# Sheet.net
KiCad netlist of a schematic drawn in Altium Designer
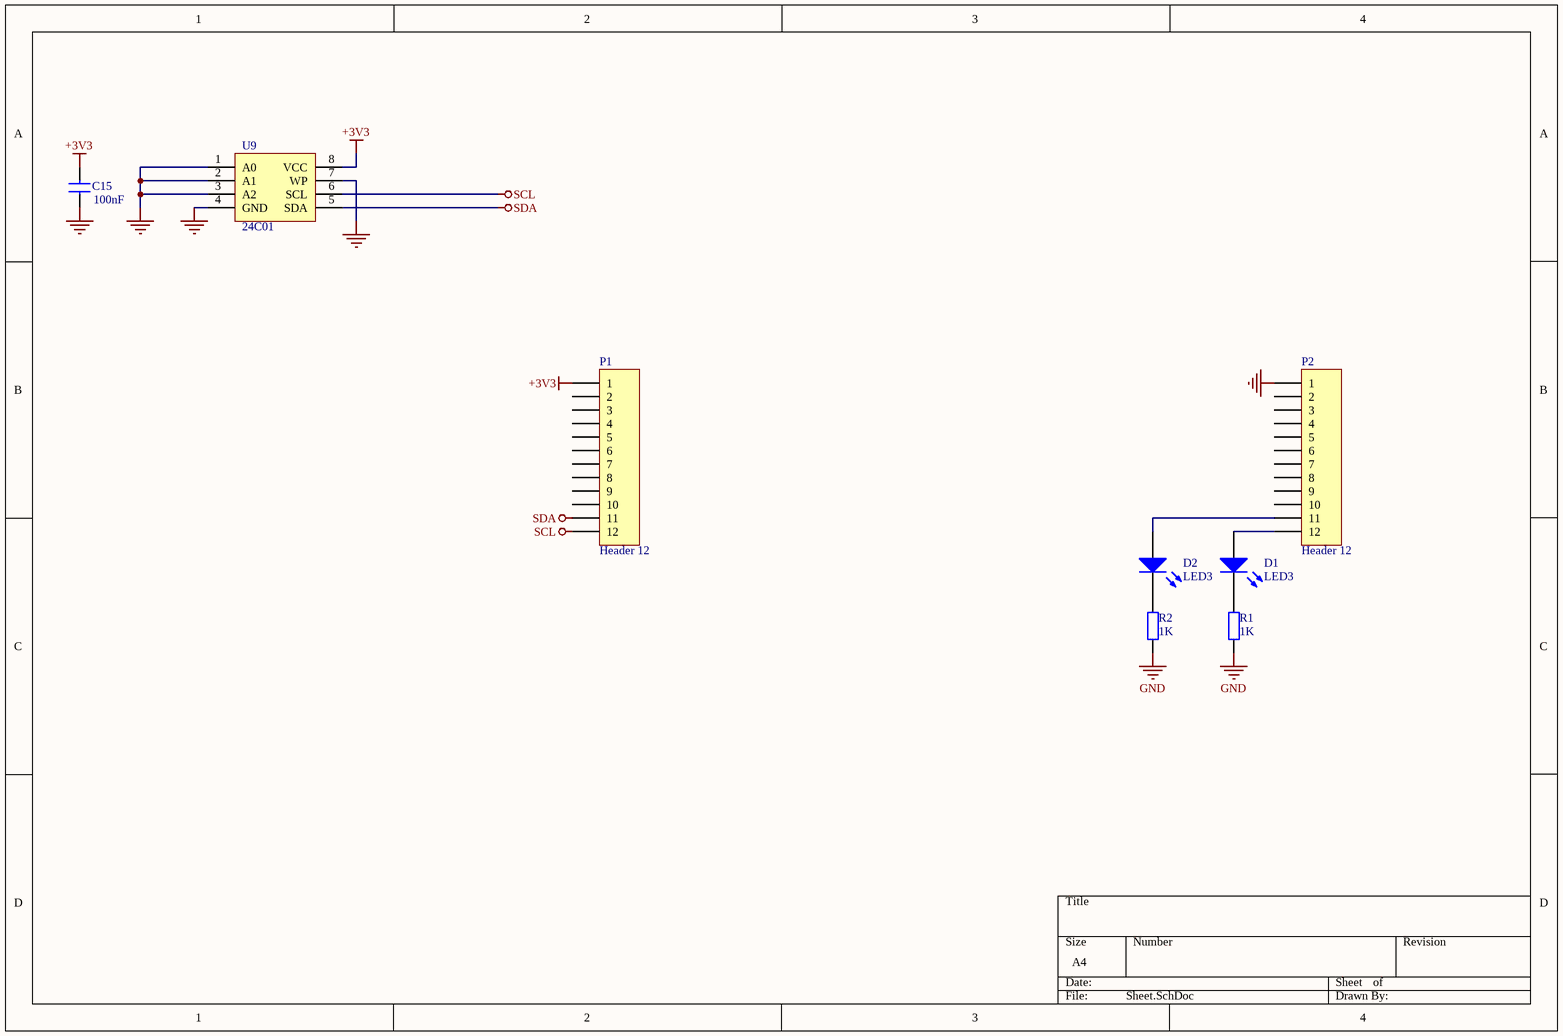
[diagram p0: Sheet.SchDoc]

(export (version "E")
  (design (tool "Eeschema 10.0.6"))
  (components
    (comp (ref "C15")
      (value "100nF")
      (footprint "RESC2012X65M")
      (description "Capacitor")
      (libsource (lib "*") (part "CAP"))
    )
    (comp (ref "D1")
      (value "LED3")
      (footprint "Led 0805")
      (description "Typical BLUE SiC LED")
      (fields (field (name "PUBLISHER") "Altium Limited"))
      (libsource (lib "Miscellaneous Devices") (part "LED3"))
    )
    (comp (ref "D2")
      (value "LED3")
      (footprint "Led 0805")
      (description "Typical BLUE SiC LED")
      (fields (field (name "PUBLISHER") "Altium Limited"))
      (libsource (lib "Miscellaneous Devices") (part "LED3"))
    )
    (comp (ref "P1")
      (value "Header 12")
      (footprint "HDR1X12")
      (description "Header, 12-Pin")
      (fields (field (name "PUBLISHER") "Altium Limited"))
      (libsource (lib "Miscellaneous Connectors") (part "Header 12"))
    )
    (comp (ref "P2")
      (value "Header 12")
      (footprint "HDR1X12")
      (description "Header, 12-Pin")
      (fields (field (name "PUBLISHER") "Altium Limited"))
      (libsource (lib "Miscellaneous Connectors") (part "Header 12"))
    )
    (comp (ref "R1")
      (value "1K")
      (footprint "0805")
      (description "Resistor")
      (fields (field (name "PUBLISHER") "Altium Limited"))
      (libsource (lib "Miscellaneous Devices") (part "Res2"))
    )
    (comp (ref "R2")
      (value "1K")
      (footprint "0805")
      (description "Resistor")
      (fields (field (name "PUBLISHER") "Altium Limited"))
      (libsource (lib "Miscellaneous Devices") (part "Res2"))
    )
    (comp (ref "U9") (value "24C01") (footprint "SO-8") (libsource (lib "Schlib1") (part "24C01")))
  )
  (nets
    (net (code "1") (name "+3V3") (class "Default")
      (node (ref "C15") (pin "1") (pinfunction "1_1") (pintype "passive"))
      (node (ref "P1") (pin "1") (pinfunction "1_1") (pintype "passive"))
      (node (ref "U9") (pin "8") (pinfunction "VCC_8") (pintype "power_in"))
    )
    (net (code "2") (name "GND") (class "Default")
      (node (ref "C15") (pin "2") (pinfunction "2_2") (pintype "passive"))
      (node (ref "P2") (pin "1") (pinfunction "1_1") (pintype "passive"))
      (node (ref "R1") (pin "1") (pinfunction "1_1") (pintype "passive"))
      (node (ref "R2") (pin "1") (pinfunction "1_1") (pintype "passive"))
      (node (ref "U9") (pin "1") (pinfunction "A0_1") (pintype "passive"))
      (node (ref "U9") (pin "2") (pinfunction "A1_2") (pintype "passive"))
      (node (ref "U9") (pin "3") (pinfunction "A2_3") (pintype "passive"))
      (node (ref "U9") (pin "4") (pinfunction "GND_4") (pintype "power_in"))
      (node (ref "U9") (pin "7") (pinfunction "WP_7") (pintype "passive"))
    )
    (net (code "3") (name "Net-(D1-A)") (class "Default")
      (node (ref "D1") (pin "1") (pinfunction "A_1") (pintype "passive"))
      (node (ref "P2") (pin "12") (pinfunction "12_12") (pintype "passive"))
    )
    (net (code "4") (name "Net-(D1-K)") (class "Default")
      (node (ref "D1") (pin "2") (pinfunction "K_2") (pintype "passive"))
      (node (ref "R1") (pin "2") (pinfunction "2_2") (pintype "passive"))
    )
    (net (code "5") (name "Net-(D2-A)") (class "Default")
      (node (ref "D2") (pin "1") (pinfunction "A_1") (pintype "passive"))
      (node (ref "P2") (pin "11") (pinfunction "11_11") (pintype "passive"))
    )
    (net (code "6") (name "Net-(D2-K)") (class "Default")
      (node (ref "D2") (pin "2") (pinfunction "K_2") (pintype "passive"))
      (node (ref "R2") (pin "2") (pinfunction "2_2") (pintype "passive"))
    )
    (net (code "7") (name "SCL") (class "Default")
      (node (ref "P1") (pin "12") (pinfunction "12_12") (pintype "passive"))
      (node (ref "U9") (pin "6") (pinfunction "SCL_6") (pintype "passive"))
    )
    (net (code "8") (name "SDA") (class "Default")
      (node (ref "P1") (pin "11") (pinfunction "11_11") (pintype "passive"))
      (node (ref "U9") (pin "5") (pinfunction "SDA_5") (pintype "passive"))
    )
    (net (code "9") (name "unconnected-(P1-Pad2)") (class "Default")
      (node (ref "P1") (pin "2") (pinfunction "2_2") (pintype "passive"))
    )
    (net (code "10") (name "unconnected-(P1-Pad3)") (class "Default")
      (node (ref "P1") (pin "3") (pinfunction "3_3") (pintype "passive"))
    )
    (net (code "11") (name "unconnected-(P1-Pad4)") (class "Default")
      (node (ref "P1") (pin "4") (pinfunction "4_4") (pintype "passive"))
    )
    (net (code "12") (name "unconnected-(P1-Pad5)") (class "Default")
      (node (ref "P1") (pin "5") (pinfunction "5_5") (pintype "passive"))
    )
    (net (code "13") (name "unconnected-(P1-Pad6)") (class "Default")
      (node (ref "P1") (pin "6") (pinfunction "6_6") (pintype "passive"))
    )
    (net (code "14") (name "unconnected-(P1-Pad7)") (class "Default")
      (node (ref "P1") (pin "7") (pinfunction "7_7") (pintype "passive"))
    )
    (net (code "15") (name "unconnected-(P1-Pad8)") (class "Default")
      (node (ref "P1") (pin "8") (pinfunction "8_8") (pintype "passive"))
    )
    (net (code "16") (name "unconnected-(P1-Pad9)") (class "Default")
      (node (ref "P1") (pin "9") (pinfunction "9_9") (pintype "passive"))
    )
    (net (code "17") (name "unconnected-(P1-Pad10)") (class "Default")
      (node (ref "P1") (pin "10") (pinfunction "10_10") (pintype "passive"))
    )
    (net (code "18") (name "unconnected-(P2-Pad2)") (class "Default")
      (node (ref "P2") (pin "2") (pinfunction "2_2") (pintype "passive"))
    )
    (net (code "19") (name "unconnected-(P2-Pad3)") (class "Default")
      (node (ref "P2") (pin "3") (pinfunction "3_3") (pintype "passive"))
    )
    (net (code "20") (name "unconnected-(P2-Pad4)") (class "Default")
      (node (ref "P2") (pin "4") (pinfunction "4_4") (pintype "passive"))
    )
    (net (code "21") (name "unconnected-(P2-Pad5)") (class "Default")
      (node (ref "P2") (pin "5") (pinfunction "5_5") (pintype "passive"))
    )
    (net (code "22") (name "unconnected-(P2-Pad6)") (class "Default")
      (node (ref "P2") (pin "6") (pinfunction "6_6") (pintype "passive"))
    )
    (net (code "23") (name "unconnected-(P2-Pad7)") (class "Default")
      (node (ref "P2") (pin "7") (pinfunction "7_7") (pintype "passive"))
    )
    (net (code "24") (name "unconnected-(P2-Pad8)") (class "Default")
      (node (ref "P2") (pin "8") (pinfunction "8_8") (pintype "passive"))
    )
    (net (code "25") (name "unconnected-(P2-Pad9)") (class "Default")
      (node (ref "P2") (pin "9") (pinfunction "9_9") (pintype "passive"))
    )
    (net (code "26") (name "unconnected-(P2-Pad10)") (class "Default")
      (node (ref "P2") (pin "10") (pinfunction "10_10") (pintype "passive"))
    )
  )
)
